# DNVT2.net
KiCad netlist of a schematic drawn in EAGLE
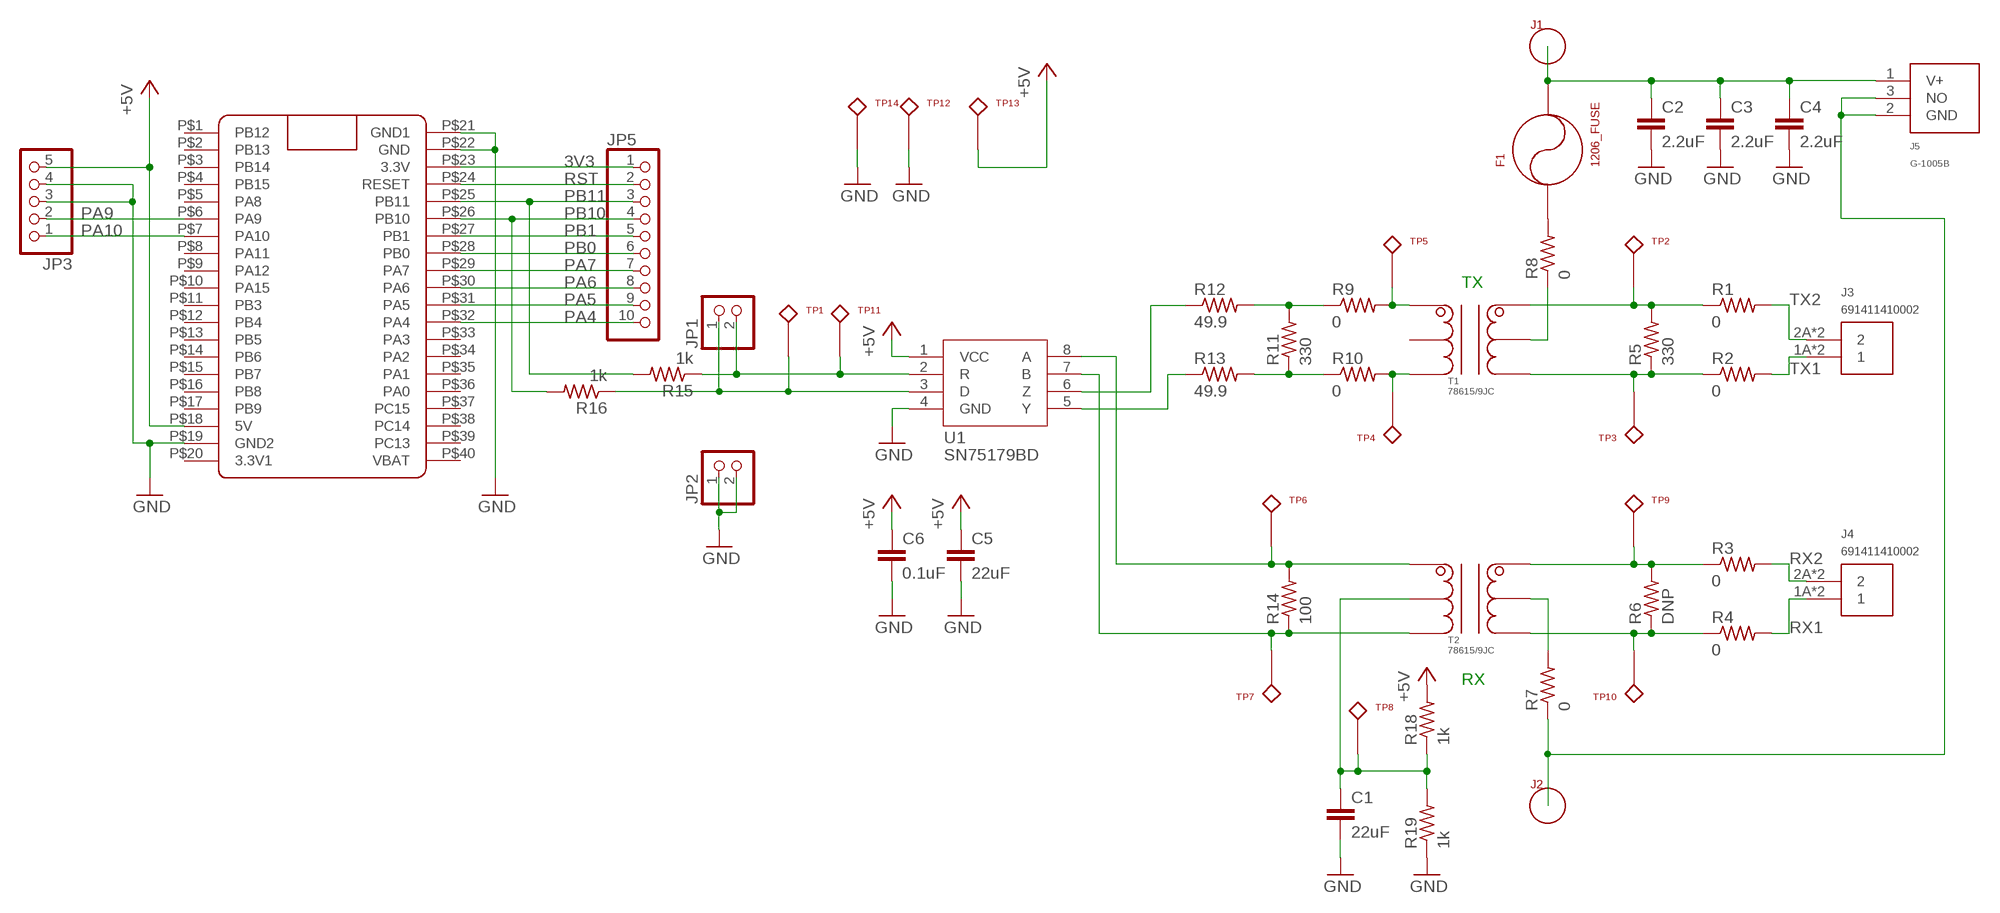
[diagram p0: schematic, sheet 1]

(export (version "E")
  (design (tool "Eeschema 10.0.6"))
  (components
    (comp (ref "C1")
      (value "22uF")
      (footprint "eagle-import:1210")
      (libsource (lib "eagle-import") (part "1210_CAPACITOR"))
    )
    (comp (ref "C2")
      (value "2.2uF")
      (footprint "eagle-import:1210")
      (libsource (lib "eagle-import") (part "1210_CAPACITOR"))
    )
    (comp (ref "C3")
      (value "2.2uF")
      (footprint "eagle-import:1210")
      (libsource (lib "eagle-import") (part "1210_CAPACITOR"))
    )
    (comp (ref "C4")
      (value "2.2uF")
      (footprint "eagle-import:1210")
      (libsource (lib "eagle-import") (part "1210_CAPACITOR"))
    )
    (comp (ref "C5")
      (value "22uF")
      (footprint "eagle-import:1210")
      (libsource (lib "eagle-import") (part "1210_CAPACITOR"))
    )
    (comp (ref "C6")
      (value "0.1uF")
      (footprint "eagle-import:0603")
      (libsource (lib "eagle-import") (part "0603_CAPACITOR"))
    )
    (comp (ref "F1")
      (value "1206_FUSE")
      (footprint "eagle-import:1206")
      (libsource (lib "eagle-import") (part "1206_FUSE"))
    )
    (comp (ref "J1")
      (value "BANANA")
      (footprint "eagle-import:BANANA")
      (fields (field (name "PARTNO") "36-575-4-ND"))
      (libsource (lib "eagle-import") (part "BANANA"))
    )
    (comp (ref "J2")
      (value "BANANA")
      (footprint "eagle-import:BANANA")
      (fields (field (name "PARTNO") "36-575-4-ND"))
      (libsource (lib "eagle-import") (part "BANANA"))
    )
    (comp (ref "J3")
      (value "691411410002")
      (footprint "eagle-import:691411410002")
      (fields (field (name "PARTNO") "732-11084-ND"))
      (libsource (lib "eagle-import") (part "691411410002"))
    )
    (comp (ref "J4")
      (value "691411410002")
      (footprint "eagle-import:691411410002")
      (fields (field (name "PARTNO") "732-11084-ND"))
      (libsource (lib "eagle-import") (part "691411410002"))
    )
    (comp (ref "J5")
      (value "G-1005B")
      (footprint "eagle-import:G-1005B")
      (fields (field (name "PARTNO") "1939-G-1005B-ND"))
      (libsource (lib "eagle-import") (part "G-1005B"))
    )
    (comp (ref "JP1")
      (value "PINHD-1X2")
      (footprint "eagle-import:1X02")
      (libsource (lib "eagle-import") (part "PINHD-1X2"))
    )
    (comp (ref "JP2")
      (value "PINHD-1X2")
      (footprint "eagle-import:1X02")
      (libsource (lib "eagle-import") (part "PINHD-1X2"))
    )
    (comp (ref "JP3")
      (value "PINHD-1X5")
      (footprint "eagle-import:1X05")
      (libsource (lib "eagle-import") (part "PINHD-1X5"))
    )
    (comp (ref "JP5")
      (value "PINHD-1X10")
      (footprint "eagle-import:1X10")
      (libsource (lib "eagle-import") (part "PINHD-1X10"))
    )
    (comp (ref "R1")
      (value "0")
      (footprint "eagle-import:R0805")
      (libsource (lib "eagle-import") (part "R-US_R0805"))
    )
    (comp (ref "R2")
      (value "0")
      (footprint "eagle-import:R0805")
      (libsource (lib "eagle-import") (part "R-US_R0805"))
    )
    (comp (ref "R3")
      (value "0")
      (footprint "eagle-import:R0805")
      (libsource (lib "eagle-import") (part "R-US_R0805"))
    )
    (comp (ref "R4")
      (value "0")
      (footprint "eagle-import:R0805")
      (libsource (lib "eagle-import") (part "R-US_R0805"))
    )
    (comp (ref "R5")
      (value "330")
      (footprint "eagle-import:R0805")
      (libsource (lib "eagle-import") (part "R-US_R0805"))
    )
    (comp (ref "R6")
      (value "DNP")
      (footprint "eagle-import:R0805")
      (libsource (lib "eagle-import") (part "R-US_R0805"))
    )
    (comp (ref "R7")
      (value "0")
      (footprint "eagle-import:R0805")
      (libsource (lib "eagle-import") (part "R-US_R0805"))
    )
    (comp (ref "R8")
      (value "0")
      (footprint "eagle-import:R0805")
      (libsource (lib "eagle-import") (part "R-US_R0805"))
    )
    (comp (ref "R9")
      (value "0")
      (footprint "eagle-import:R0805")
      (libsource (lib "eagle-import") (part "R-US_R0805"))
    )
    (comp (ref "R10")
      (value "0")
      (footprint "eagle-import:R0805")
      (libsource (lib "eagle-import") (part "R-US_R0805"))
    )
    (comp (ref "R11")
      (value "330")
      (footprint "eagle-import:R0805")
      (libsource (lib "eagle-import") (part "R-US_R0805"))
    )
    (comp (ref "R12")
      (value "49.9")
      (footprint "eagle-import:R0805")
      (libsource (lib "eagle-import") (part "R-US_R0805"))
    )
    (comp (ref "R13")
      (value "49.9")
      (footprint "eagle-import:R0805")
      (libsource (lib "eagle-import") (part "R-US_R0805"))
    )
    (comp (ref "R14")
      (value "100")
      (footprint "eagle-import:R0805")
      (libsource (lib "eagle-import") (part "R-US_R0805"))
    )
    (comp (ref "R15")
      (value "1k")
      (footprint "eagle-import:0603")
      (libsource (lib "eagle-import") (part "0603_RESISTOR"))
    )
    (comp (ref "R16")
      (value "1k")
      (footprint "eagle-import:0603")
      (libsource (lib "eagle-import") (part "0603_RESISTOR"))
    )
    (comp (ref "R18")
      (value "1k")
      (footprint "eagle-import:0603")
      (libsource (lib "eagle-import") (part "0603_RESISTOR"))
    )
    (comp (ref "R19")
      (value "1k")
      (footprint "eagle-import:0603")
      (libsource (lib "eagle-import") (part "0603_RESISTOR"))
    )
    (comp (ref "T1")
      (value "78615/9JC")
      (footprint "eagle-import:786")
      (fields (field (name "PARTNO") "811-2423-ND"))
      (libsource (lib "eagle-import") (part "78615/9JC"))
    )
    (comp (ref "T2")
      (value "78615/9JC")
      (footprint "eagle-import:786")
      (fields (field (name "PARTNO") "811-2423-ND"))
      (libsource (lib "eagle-import") (part "78615/9JC"))
    )
    (comp (ref "TP1")
      (value "5001")
      (footprint "eagle-import:5001")
      (fields (field (name "PARTNO") "36-5001-ND"))
      (libsource (lib "eagle-import") (part "5001"))
    )
    (comp (ref "TP2")
      (value "5002")
      (footprint "eagle-import:5001")
      (fields (field (name "PARTNO") "36-5002-ND"))
      (libsource (lib "eagle-import") (part "5002"))
    )
    (comp (ref "TP3")
      (value "5002")
      (footprint "eagle-import:5001")
      (fields (field (name "PARTNO") "36-5002-ND"))
      (libsource (lib "eagle-import") (part "5002"))
    )
    (comp (ref "TP4")
      (value "5002")
      (footprint "eagle-import:5001")
      (fields (field (name "PARTNO") "36-5002-ND"))
      (libsource (lib "eagle-import") (part "5002"))
    )
    (comp (ref "TP5")
      (value "5002")
      (footprint "eagle-import:5001")
      (fields (field (name "PARTNO") "36-5002-ND"))
      (libsource (lib "eagle-import") (part "5002"))
    )
    (comp (ref "TP6")
      (value "5002")
      (footprint "eagle-import:5001")
      (fields (field (name "PARTNO") "36-5002-ND"))
      (libsource (lib "eagle-import") (part "5002"))
    )
    (comp (ref "TP7")
      (value "5002")
      (footprint "eagle-import:5001")
      (fields (field (name "PARTNO") "36-5002-ND"))
      (libsource (lib "eagle-import") (part "5002"))
    )
    (comp (ref "TP8")
      (value "5002")
      (footprint "eagle-import:5001")
      (fields (field (name "PARTNO") "36-5002-ND"))
      (libsource (lib "eagle-import") (part "5002"))
    )
    (comp (ref "TP9")
      (value "5002")
      (footprint "eagle-import:5001")
      (fields (field (name "PARTNO") "36-5002-ND"))
      (libsource (lib "eagle-import") (part "5002"))
    )
    (comp (ref "TP10")
      (value "5002")
      (footprint "eagle-import:5001")
      (fields (field (name "PARTNO") "36-5002-ND"))
      (libsource (lib "eagle-import") (part "5002"))
    )
    (comp (ref "TP11")
      (value "5001")
      (footprint "eagle-import:5001")
      (fields (field (name "PARTNO") "36-5001-ND"))
      (libsource (lib "eagle-import") (part "5001"))
    )
    (comp (ref "TP12")
      (value "5001")
      (footprint "eagle-import:5001")
      (fields (field (name "PARTNO") "36-5001-ND"))
      (libsource (lib "eagle-import") (part "5001"))
    )
    (comp (ref "TP13")
      (value "5001")
      (footprint "eagle-import:5001")
      (fields (field (name "PARTNO") "36-5001-ND"))
      (libsource (lib "eagle-import") (part "5001"))
    )
    (comp (ref "TP14")
      (value "5001")
      (footprint "eagle-import:5001")
      (fields (field (name "PARTNO") "36-5001-ND"))
      (libsource (lib "eagle-import") (part "5001"))
    )
    (comp (ref "U$1")
      (value "BLUE_PILL")
      (footprint "eagle-import:BLUE_PILL")
      (libsource (lib "eagle-import") (part "BLUE_PILL"))
    )
    (comp (ref "U1")
      (value "SN75179BD")
      (footprint "eagle-import:SOIC8")
      (fields (field (name "PARTNO") "296-6860-5-ND"))
      (libsource (lib "eagle-import") (part "SN75179BD"))
    )
  )
  (nets
    (net (code "1") (name "+5V") (class "Default")
      (node (ref "C5") (pin "1") (pinfunction "1_1") (pintype "passive"))
      (node (ref "C6") (pin "1") (pinfunction "1_1") (pintype "passive"))
      (node (ref "JP3") (pin "5") (pinfunction "5_5") (pintype "passive"))
      (node (ref "R18") (pin "2") (pinfunction "2_2") (pintype "passive"))
      (node (ref "TP13") (pin "P$1") (pinfunction "P$1_P$1") (pintype "bidirectional"))
      (node (ref "U$1") (pin "P$18") (pinfunction "5V_P$18") (pintype "bidirectional"))
      (node (ref "U1") (pin "1") (pinfunction "VCC_1") (pintype "bidirectional"))
    )
    (net (code "2") (name "/3V3") (class "Default")
      (node (ref "JP5") (pin "1") (pinfunction "1_1") (pintype "passive"))
      (node (ref "U$1") (pin "P$23") (pinfunction "3.3V_P$23") (pintype "bidirectional"))
    )
    (net (code "3") (name "/PA4") (class "Default")
      (node (ref "JP5") (pin "10") (pinfunction "10_10") (pintype "passive"))
      (node (ref "U$1") (pin "P$32") (pinfunction "PA4_P$32") (pintype "bidirectional"))
    )
    (net (code "4") (name "/PA5") (class "Default")
      (node (ref "JP5") (pin "9") (pinfunction "9_9") (pintype "passive"))
      (node (ref "U$1") (pin "P$31") (pinfunction "PA5_P$31") (pintype "bidirectional"))
    )
    (net (code "5") (name "/PA6") (class "Default")
      (node (ref "JP5") (pin "8") (pinfunction "8_8") (pintype "passive"))
      (node (ref "U$1") (pin "P$30") (pinfunction "PA6_P$30") (pintype "bidirectional"))
    )
    (net (code "6") (name "/PA7") (class "Default")
      (node (ref "JP5") (pin "7") (pinfunction "7_7") (pintype "passive"))
      (node (ref "U$1") (pin "P$29") (pinfunction "PA7_P$29") (pintype "bidirectional"))
    )
    (net (code "7") (name "/PA9") (class "Default")
      (node (ref "JP3") (pin "2") (pinfunction "2_2") (pintype "passive"))
      (node (ref "U$1") (pin "P$6") (pinfunction "PA9_P$6") (pintype "bidirectional"))
    )
    (net (code "8") (name "/PA10") (class "Default")
      (node (ref "JP3") (pin "1") (pinfunction "1_1") (pintype "passive"))
      (node (ref "U$1") (pin "P$7") (pinfunction "PA10_P$7") (pintype "bidirectional"))
    )
    (net (code "9") (name "/PB0") (class "Default")
      (node (ref "JP5") (pin "6") (pinfunction "6_6") (pintype "passive"))
      (node (ref "U$1") (pin "P$28") (pinfunction "PB0_P$28") (pintype "bidirectional"))
    )
    (net (code "10") (name "/PB1") (class "Default")
      (node (ref "JP5") (pin "5") (pinfunction "5_5") (pintype "passive"))
      (node (ref "U$1") (pin "P$27") (pinfunction "PB1_P$27") (pintype "bidirectional"))
    )
    (net (code "11") (name "/PB10") (class "Default")
      (node (ref "JP5") (pin "4") (pinfunction "4_4") (pintype "passive"))
      (node (ref "R16") (pin "2") (pinfunction "2_2") (pintype "passive"))
      (node (ref "U$1") (pin "P$26") (pinfunction "PB10_P$26") (pintype "bidirectional"))
    )
    (net (code "12") (name "/PB11") (class "Default")
      (node (ref "JP5") (pin "3") (pinfunction "3_3") (pintype "passive"))
      (node (ref "R15") (pin "2") (pinfunction "2_2") (pintype "passive"))
      (node (ref "U$1") (pin "P$25") (pinfunction "PB11_P$25") (pintype "bidirectional"))
    )
    (net (code "13") (name "/RST") (class "Default")
      (node (ref "JP5") (pin "2") (pinfunction "2_2") (pintype "passive"))
      (node (ref "U$1") (pin "P$24") (pinfunction "RESET_P$24") (pintype "bidirectional"))
    )
    (net (code "14") (name "/RX1") (class "Default")
      (node (ref "J4") (pin "1A") (pinfunction "1_1A") (pintype "bidirectional"))
      (node (ref "J4") (pin "1B") (pinfunction "1_1B") (pintype "bidirectional"))
      (node (ref "R4") (pin "2") (pinfunction "2_2") (pintype "passive"))
    )
    (net (code "15") (name "/RX2") (class "Default")
      (node (ref "J4") (pin "2A") (pinfunction "2_2A") (pintype "bidirectional"))
      (node (ref "J4") (pin "2B") (pinfunction "2_2B") (pintype "bidirectional"))
      (node (ref "R3") (pin "2") (pinfunction "2_2") (pintype "passive"))
    )
    (net (code "16") (name "/TX1") (class "Default")
      (node (ref "J3") (pin "1A") (pinfunction "1_1A") (pintype "bidirectional"))
      (node (ref "J3") (pin "1B") (pinfunction "1_1B") (pintype "bidirectional"))
      (node (ref "R2") (pin "2") (pinfunction "2_2") (pintype "passive"))
    )
    (net (code "17") (name "/TX2") (class "Default")
      (node (ref "J3") (pin "2A") (pinfunction "2_2A") (pintype "bidirectional"))
      (node (ref "J3") (pin "2B") (pinfunction "2_2B") (pintype "bidirectional"))
      (node (ref "R1") (pin "2") (pinfunction "2_2") (pintype "passive"))
    )
    (net (code "18") (name "GND") (class "Default")
      (node (ref "C1") (pin "2") (pinfunction "2_2") (pintype "passive"))
      (node (ref "C2") (pin "2") (pinfunction "2_2") (pintype "passive"))
      (node (ref "C3") (pin "2") (pinfunction "2_2") (pintype "passive"))
      (node (ref "C4") (pin "2") (pinfunction "2_2") (pintype "passive"))
      (node (ref "C5") (pin "2") (pinfunction "2_2") (pintype "passive"))
      (node (ref "C6") (pin "2") (pinfunction "2_2") (pintype "passive"))
      (node (ref "JP2") (pin "1") (pinfunction "1_1") (pintype "passive"))
      (node (ref "JP2") (pin "2") (pinfunction "2_2") (pintype "passive"))
      (node (ref "JP3") (pin "3") (pinfunction "3_3") (pintype "passive"))
      (node (ref "JP3") (pin "4") (pinfunction "4_4") (pintype "passive"))
      (node (ref "R19") (pin "1") (pinfunction "1_1") (pintype "passive"))
      (node (ref "TP12") (pin "P$1") (pinfunction "P$1_P$1") (pintype "bidirectional"))
      (node (ref "TP14") (pin "P$1") (pinfunction "P$1_P$1") (pintype "bidirectional"))
      (node (ref "U$1") (pin "P$19") (pinfunction "GND2_P$19") (pintype "bidirectional"))
      (node (ref "U$1") (pin "P$21") (pinfunction "GND1_P$21") (pintype "power_in"))
      (node (ref "U$1") (pin "P$22") (pinfunction "GND_P$22") (pintype "bidirectional"))
      (node (ref "U1") (pin "4") (pinfunction "GND_4") (pintype "bidirectional"))
    )
    (net (code "19") (name "Net-(C1-Pad1)") (class "Default")
      (node (ref "C1") (pin "1") (pinfunction "1_1") (pintype "passive"))
      (node (ref "R18") (pin "1") (pinfunction "1_1") (pintype "passive"))
      (node (ref "R19") (pin "2") (pinfunction "2_2") (pintype "passive"))
      (node (ref "T2") (pin "2") (pinfunction "2_2") (pintype "bidirectional"))
      (node (ref "TP8") (pin "P$1") (pinfunction "P$1_P$1") (pintype "bidirectional"))
    )
    (net (code "20") (name "Net-(F1-P$1)") (class "Default")
      (node (ref "F1") (pin "1") (pinfunction "P$1_1") (pintype "bidirectional"))
      (node (ref "R8") (pin "2") (pinfunction "2_2") (pintype "passive"))
    )
    (net (code "21") (name "Net-(F1-P$2)") (class "Default")
      (node (ref "C2") (pin "1") (pinfunction "1_1") (pintype "passive"))
      (node (ref "C3") (pin "1") (pinfunction "1_1") (pintype "passive"))
      (node (ref "C4") (pin "1") (pinfunction "1_1") (pintype "passive"))
      (node (ref "F1") (pin "2") (pinfunction "P$2_2") (pintype "bidirectional"))
      (node (ref "J1") (pin "P$1") (pinfunction "P$1_P$1") (pintype "bidirectional"))
      (node (ref "J5") (pin "1") (pinfunction "V+_1") (pintype "bidirectional"))
    )
    (net (code "22") (name "Net-(J5-GND)") (class "Default")
      (node (ref "J2") (pin "P$1") (pinfunction "P$1_P$1") (pintype "bidirectional"))
      (node (ref "J5") (pin "2") (pinfunction "GND_2") (pintype "bidirectional"))
      (node (ref "J5") (pin "3") (pinfunction "NO_3") (pintype "bidirectional"))
      (node (ref "R7") (pin "1") (pinfunction "1_1") (pintype "passive"))
    )
    (net (code "23") (name "Net-(R1-Pad1)") (class "Default")
      (node (ref "R1") (pin "1") (pinfunction "1_1") (pintype "passive"))
      (node (ref "R5") (pin "2") (pinfunction "2_2") (pintype "passive"))
      (node (ref "T1") (pin "6") (pinfunction "6_6") (pintype "bidirectional"))
      (node (ref "TP2") (pin "P$1") (pinfunction "P$1_P$1") (pintype "bidirectional"))
    )
    (net (code "24") (name "Net-(R2-Pad1)") (class "Default")
      (node (ref "R2") (pin "1") (pinfunction "1_1") (pintype "passive"))
      (node (ref "R5") (pin "1") (pinfunction "1_1") (pintype "passive"))
      (node (ref "T1") (pin "4") (pinfunction "4_4") (pintype "bidirectional"))
      (node (ref "TP3") (pin "P$1") (pinfunction "P$1_P$1") (pintype "bidirectional"))
    )
    (net (code "25") (name "Net-(R3-Pad1)") (class "Default")
      (node (ref "R3") (pin "1") (pinfunction "1_1") (pintype "passive"))
      (node (ref "R6") (pin "2") (pinfunction "2_2") (pintype "passive"))
      (node (ref "T2") (pin "6") (pinfunction "6_6") (pintype "bidirectional"))
      (node (ref "TP9") (pin "P$1") (pinfunction "P$1_P$1") (pintype "bidirectional"))
    )
    (net (code "26") (name "Net-(R4-Pad1)") (class "Default")
      (node (ref "R4") (pin "1") (pinfunction "1_1") (pintype "passive"))
      (node (ref "R6") (pin "1") (pinfunction "1_1") (pintype "passive"))
      (node (ref "T2") (pin "4") (pinfunction "4_4") (pintype "bidirectional"))
      (node (ref "TP10") (pin "P$1") (pinfunction "P$1_P$1") (pintype "bidirectional"))
    )
    (net (code "27") (name "Net-(R7-Pad2)") (class "Default")
      (node (ref "R7") (pin "2") (pinfunction "2_2") (pintype "passive"))
      (node (ref "T2") (pin "5") (pinfunction "5_5") (pintype "bidirectional"))
    )
    (net (code "28") (name "Net-(R8-Pad1)") (class "Default")
      (node (ref "R8") (pin "1") (pinfunction "1_1") (pintype "passive"))
      (node (ref "T1") (pin "5") (pinfunction "5_5") (pintype "bidirectional"))
    )
    (net (code "29") (name "Net-(R9-Pad2)") (class "Default")
      (node (ref "R9") (pin "2") (pinfunction "2_2") (pintype "passive"))
      (node (ref "T1") (pin "1") (pinfunction "1_1") (pintype "bidirectional"))
      (node (ref "TP5") (pin "P$1") (pinfunction "P$1_P$1") (pintype "bidirectional"))
    )
    (net (code "30") (name "Net-(R10-Pad1)") (class "Default")
      (node (ref "R10") (pin "1") (pinfunction "1_1") (pintype "passive"))
      (node (ref "R11") (pin "1") (pinfunction "1_1") (pintype "passive"))
      (node (ref "R13") (pin "2") (pinfunction "2_2") (pintype "passive"))
    )
    (net (code "31") (name "Net-(R10-Pad2)") (class "Default")
      (node (ref "R10") (pin "2") (pinfunction "2_2") (pintype "passive"))
      (node (ref "T1") (pin "3") (pinfunction "3_3") (pintype "bidirectional"))
      (node (ref "TP4") (pin "P$1") (pinfunction "P$1_P$1") (pintype "bidirectional"))
    )
    (net (code "32") (name "Net-(R11-Pad2)") (class "Default")
      (node (ref "R11") (pin "2") (pinfunction "2_2") (pintype "passive"))
      (node (ref "R12") (pin "2") (pinfunction "2_2") (pintype "passive"))
      (node (ref "R9") (pin "1") (pinfunction "1_1") (pintype "passive"))
    )
    (net (code "33") (name "Net-(U1-A)") (class "Default")
      (node (ref "R14") (pin "2") (pinfunction "2_2") (pintype "passive"))
      (node (ref "T2") (pin "1") (pinfunction "1_1") (pintype "bidirectional"))
      (node (ref "TP6") (pin "P$1") (pinfunction "P$1_P$1") (pintype "bidirectional"))
      (node (ref "U1") (pin "8") (pinfunction "A_8") (pintype "bidirectional"))
    )
    (net (code "34") (name "Net-(U1-B)") (class "Default")
      (node (ref "R14") (pin "1") (pinfunction "1_1") (pintype "passive"))
      (node (ref "T2") (pin "3") (pinfunction "3_3") (pintype "bidirectional"))
      (node (ref "TP7") (pin "P$1") (pinfunction "P$1_P$1") (pintype "bidirectional"))
      (node (ref "U1") (pin "7") (pinfunction "B_7") (pintype "bidirectional"))
    )
    (net (code "35") (name "Net-(U1-D)") (class "Default")
      (node (ref "JP1") (pin "1") (pinfunction "1_1") (pintype "passive"))
      (node (ref "R16") (pin "1") (pinfunction "1_1") (pintype "passive"))
      (node (ref "TP1") (pin "P$1") (pinfunction "P$1_P$1") (pintype "bidirectional"))
      (node (ref "U1") (pin "3") (pinfunction "D_3") (pintype "bidirectional"))
    )
    (net (code "36") (name "Net-(U1-R)") (class "Default")
      (node (ref "JP1") (pin "2") (pinfunction "2_2") (pintype "passive"))
      (node (ref "R15") (pin "1") (pinfunction "1_1") (pintype "passive"))
      (node (ref "TP11") (pin "P$1") (pinfunction "P$1_P$1") (pintype "bidirectional"))
      (node (ref "U1") (pin "2") (pinfunction "R_2") (pintype "bidirectional"))
    )
    (net (code "37") (name "Net-(U1-Y)") (class "Default")
      (node (ref "R13") (pin "1") (pinfunction "1_1") (pintype "passive"))
      (node (ref "U1") (pin "5") (pinfunction "Y_5") (pintype "bidirectional"))
    )
    (net (code "38") (name "Net-(U1-Z)") (class "Default")
      (node (ref "R12") (pin "1") (pinfunction "1_1") (pintype "passive"))
      (node (ref "U1") (pin "6") (pinfunction "Z_6") (pintype "bidirectional"))
    )
    (net (code "39") (name "unconnected-(T1-Pad2)") (class "Default")
      (node (ref "T1") (pin "2") (pinfunction "2_2") (pintype "bidirectional"))
    )
    (net (code "40") (name "unconnected-(U$1-3.3V1-PadP$20)") (class "Default")
      (node (ref "U$1") (pin "P$20") (pinfunction "3.3V1_P$20") (pintype "bidirectional"))
    )
    (net (code "41") (name "unconnected-(U$1-PA0-PadP$36)") (class "Default")
      (node (ref "U$1") (pin "P$36") (pinfunction "PA0_P$36") (pintype "bidirectional"))
    )
    (net (code "42") (name "unconnected-(U$1-PA1-PadP$35)") (class "Default")
      (node (ref "U$1") (pin "P$35") (pinfunction "PA1_P$35") (pintype "bidirectional"))
    )
    (net (code "43") (name "unconnected-(U$1-PA2-PadP$34)") (class "Default")
      (node (ref "U$1") (pin "P$34") (pinfunction "PA2_P$34") (pintype "bidirectional"))
    )
    (net (code "44") (name "unconnected-(U$1-PA3-PadP$33)") (class "Default")
      (node (ref "U$1") (pin "P$33") (pinfunction "PA3_P$33") (pintype "bidirectional"))
    )
    (net (code "45") (name "unconnected-(U$1-PA8-PadP$5)") (class "Default")
      (node (ref "U$1") (pin "P$5") (pinfunction "PA8_P$5") (pintype "bidirectional"))
    )
    (net (code "46") (name "unconnected-(U$1-PA11-PadP$8)") (class "Default")
      (node (ref "U$1") (pin "P$8") (pinfunction "PA11_P$8") (pintype "bidirectional"))
    )
    (net (code "47") (name "unconnected-(U$1-PA12-PadP$9)") (class "Default")
      (node (ref "U$1") (pin "P$9") (pinfunction "PA12_P$9") (pintype "bidirectional"))
    )
    (net (code "48") (name "unconnected-(U$1-PA15-PadP$10)") (class "Default")
      (node (ref "U$1") (pin "P$10") (pinfunction "PA15_P$10") (pintype "bidirectional"))
    )
    (net (code "49") (name "unconnected-(U$1-PB3-PadP$11)") (class "Default")
      (node (ref "U$1") (pin "P$11") (pinfunction "PB3_P$11") (pintype "bidirectional"))
    )
    (net (code "50") (name "unconnected-(U$1-PB4-PadP$12)") (class "Default")
      (node (ref "U$1") (pin "P$12") (pinfunction "PB4_P$12") (pintype "bidirectional"))
    )
    (net (code "51") (name "unconnected-(U$1-PB5-PadP$13)") (class "Default")
      (node (ref "U$1") (pin "P$13") (pinfunction "PB5_P$13") (pintype "bidirectional"))
    )
    (net (code "52") (name "unconnected-(U$1-PB6-PadP$14)") (class "Default")
      (node (ref "U$1") (pin "P$14") (pinfunction "PB6_P$14") (pintype "bidirectional"))
    )
    (net (code "53") (name "unconnected-(U$1-PB7-PadP$15)") (class "Default")
      (node (ref "U$1") (pin "P$15") (pinfunction "PB7_P$15") (pintype "bidirectional"))
    )
    (net (code "54") (name "unconnected-(U$1-PB8-PadP$16)") (class "Default")
      (node (ref "U$1") (pin "P$16") (pinfunction "PB8_P$16") (pintype "bidirectional"))
    )
    (net (code "55") (name "unconnected-(U$1-PB9-PadP$17)") (class "Default")
      (node (ref "U$1") (pin "P$17") (pinfunction "PB9_P$17") (pintype "bidirectional"))
    )
    (net (code "56") (name "unconnected-(U$1-PB12-PadP$1)") (class "Default")
      (node (ref "U$1") (pin "P$1") (pinfunction "PB12_P$1") (pintype "bidirectional"))
    )
    (net (code "57") (name "unconnected-(U$1-PB13-PadP$2)") (class "Default")
      (node (ref "U$1") (pin "P$2") (pinfunction "PB13_P$2") (pintype "bidirectional"))
    )
    (net (code "58") (name "unconnected-(U$1-PB14-PadP$3)") (class "Default")
      (node (ref "U$1") (pin "P$3") (pinfunction "PB14_P$3") (pintype "bidirectional"))
    )
    (net (code "59") (name "unconnected-(U$1-PB15-PadP$4)") (class "Default")
      (node (ref "U$1") (pin "P$4") (pinfunction "PB15_P$4") (pintype "bidirectional"))
    )
    (net (code "60") (name "unconnected-(U$1-PC13-PadP$39)") (class "Default")
      (node (ref "U$1") (pin "P$39") (pinfunction "PC13_P$39") (pintype "bidirectional"))
    )
    (net (code "61") (name "unconnected-(U$1-PC14-PadP$38)") (class "Default")
      (node (ref "U$1") (pin "P$38") (pinfunction "PC14_P$38") (pintype "bidirectional"))
    )
    (net (code "62") (name "unconnected-(U$1-PC15-PadP$37)") (class "Default")
      (node (ref "U$1") (pin "P$37") (pinfunction "PC15_P$37") (pintype "bidirectional"))
    )
    (net (code "63") (name "unconnected-(U$1-VBAT-PadP$40)") (class "Default")
      (node (ref "U$1") (pin "P$40") (pinfunction "VBAT_P$40") (pintype "bidirectional"))
    )
  )
)
